# PocketQube.net
KiCad netlist of a schematic drawn in EAGLE
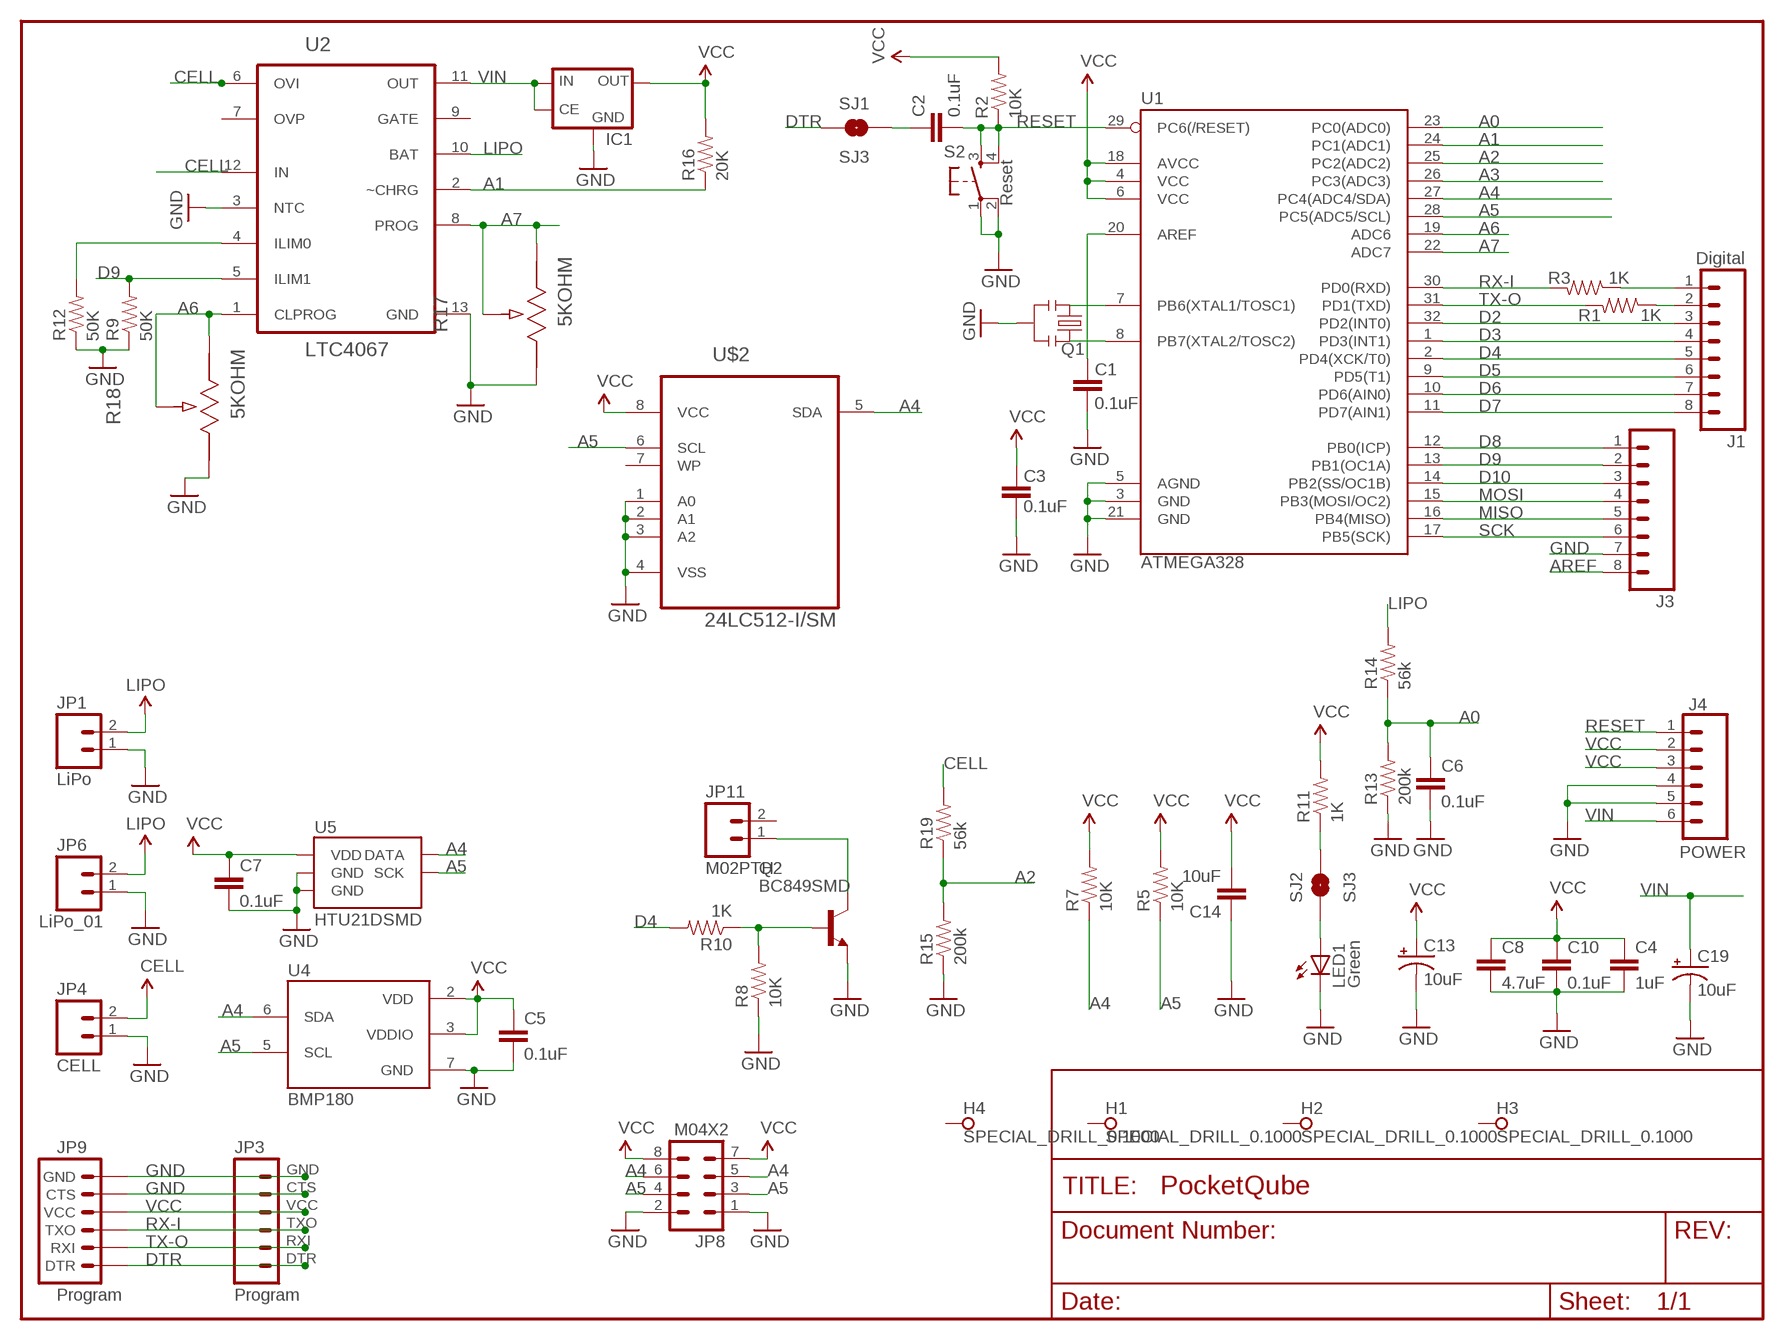
[diagram p0: schematic, sheet 1]

(export (version "E")
  (design (tool "Eeschema 10.0.6"))
  (components
    (comp (ref "C1")
      (value "0.1uF")
      (footprint "eagle-import:0805")
      (libsource (lib "eagle-import") (part "CAP0805"))
    )
    (comp (ref "C2")
      (value "0.1uF")
      (footprint "eagle-import:0805")
      (libsource (lib "eagle-import") (part "CAP0805"))
    )
    (comp (ref "C3")
      (value "0.1uF")
      (footprint "eagle-import:0805")
      (libsource (lib "eagle-import") (part "CAP0805"))
    )
    (comp (ref "C4")
      (value "1uF")
      (footprint "eagle-import:0805")
      (libsource (lib "eagle-import") (part "CAP0805"))
    )
    (comp (ref "C5")
      (value "0.1uF")
      (footprint "eagle-import:0805")
      (libsource (lib "eagle-import") (part "CAP0805"))
    )
    (comp (ref "C6")
      (value "0.1uF")
      (footprint "eagle-import:0805")
      (libsource (lib "eagle-import") (part "CAP0805"))
    )
    (comp (ref "C7")
      (value "0.1uF")
      (footprint "eagle-import:0805")
      (libsource (lib "eagle-import") (part "CAP0805"))
    )
    (comp (ref "C8")
      (value "4.7uF")
      (footprint "eagle-import:0805")
      (libsource (lib "eagle-import") (part "CAP0805"))
    )
    (comp (ref "C10")
      (value "0.1uF")
      (footprint "eagle-import:0805")
      (libsource (lib "eagle-import") (part "CAP0805"))
    )
    (comp (ref "C13")
      (value "10uF")
      (footprint "eagle-import:EIA3216")
      (libsource (lib "eagle-import") (part "CAP_POL1206"))
    )
    (comp (ref "C14")
      (value "10uF")
      (footprint "eagle-import:0805")
      (libsource (lib "eagle-import") (part "SparkFun-Passives_CAP0805"))
    )
    (comp (ref "C19")
      (value "10uF")
      (footprint "eagle-import:EIA3216")
      (libsource (lib "eagle-import") (part "CAP_POL1206"))
    )
    (comp (ref "H1")
      (value "SPECIAL_DRILL_0.1000")
      (footprint "eagle-import:PAD_0.1000")
      (libsource (lib "eagle-import") (part "SPECIAL_DRILL_0.1000"))
    )
    (comp (ref "H2")
      (value "SPECIAL_DRILL_0.1000")
      (footprint "eagle-import:PAD_0.1000")
      (libsource (lib "eagle-import") (part "SPECIAL_DRILL_0.1000"))
    )
    (comp (ref "H3")
      (value "SPECIAL_DRILL_0.1000")
      (footprint "eagle-import:PAD_0.1000")
      (libsource (lib "eagle-import") (part "SPECIAL_DRILL_0.1000"))
    )
    (comp (ref "H4")
      (value "SPECIAL_DRILL_0.1000")
      (footprint "eagle-import:PAD_0.1000")
      (libsource (lib "eagle-import") (part "SPECIAL_DRILL_0.1000"))
    )
    (comp (ref "IC1")
      (value "XC63FPP")
      (footprint "eagle-import:SOT89R")
      (libsource (lib "eagle-import") (part "XC63FPP"))
    )
    (comp (ref "J1")
      (value "Digital")
      (footprint "eagle-import:1X08")
      (libsource (lib "eagle-import") (part "M081X08"))
    )
    (comp (ref "J3")
      (value "M081X08")
      (footprint "eagle-import:1X08")
      (libsource (lib "eagle-import") (part "M081X08"))
    )
    (comp (ref "J4")
      (value "POWER")
      (footprint "eagle-import:1X06")
      (libsource (lib "eagle-import") (part "M06SIP"))
    )
    (comp (ref "JP1")
      (value "LiPo")
      (footprint "eagle-import:1X02")
      (libsource (lib "eagle-import") (part "SparkFun-Connectors_M02PTH"))
    )
    (comp (ref "JP3")
      (value "Program")
      (footprint "eagle-import:1X06")
      (libsource (lib "eagle-import") (part "SparkFun-Connectors_M06SIP"))
    )
    (comp (ref "JP4")
      (value "CELL")
      (footprint "eagle-import:1X02")
      (libsource (lib "eagle-import") (part "SparkFun-Connectors_M02PTH"))
    )
    (comp (ref "JP6")
      (value "LiPo_01")
      (footprint "eagle-import:1X02")
      (libsource (lib "eagle-import") (part "M02PTH"))
    )
    (comp (ref "JP8")
      (value "M04X2")
      (footprint "eagle-import:2X4")
      (libsource (lib "eagle-import") (part "M04X2"))
    )
    (comp (ref "JP9")
      (value "Program")
      (footprint "eagle-import:1X06-SMD")
      (libsource (lib "eagle-import") (part "ARDUINO_SERIAL_PROGRAMSMD"))
    )
    (comp (ref "JP11")
      (value "M02PTH")
      (footprint "eagle-import:1X02")
      (libsource (lib "eagle-import") (part "SparkFun-Connectors_M02PTH"))
    )
    (comp (ref "LED1")
      (value "Green")
      (footprint "eagle-import:PLCC2")
      (libsource (lib "eagle-import") (part "_T679-?-1E1F1LG"))
    )
    (comp (ref "Q1")
      (value "8MHZ")
      (footprint "eagle-import:RESONATOR-SMD")
      (libsource (lib "eagle-import") (part "RESONATOR8MHZ"))
    )
    (comp (ref "Q2")
      (value "BC849SMD")
      (footprint "eagle-import:SOT23-BEC")
      (libsource (lib "eagle-import") (part "BC849SMD"))
    )
    (comp (ref "R1")
      (value "1K")
      (footprint "eagle-import:0805")
      (libsource (lib "eagle-import") (part "RESISTOR0805-RES"))
    )
    (comp (ref "R2")
      (value "10K")
      (footprint "eagle-import:0805")
      (libsource (lib "eagle-import") (part "RESISTOR0805-RES"))
    )
    (comp (ref "R3")
      (value "1K")
      (footprint "eagle-import:0805")
      (libsource (lib "eagle-import") (part "RESISTOR0805-RES"))
    )
    (comp (ref "R5")
      (value "10K")
      (footprint "eagle-import:0805")
      (libsource (lib "eagle-import") (part "RESISTOR0805-RES"))
    )
    (comp (ref "R7")
      (value "10K")
      (footprint "eagle-import:0805")
      (libsource (lib "eagle-import") (part "RESISTOR0805-RES"))
    )
    (comp (ref "R8")
      (value "10K")
      (footprint "eagle-import:0805")
      (libsource (lib "eagle-import") (part "RESISTOR0805-RES"))
    )
    (comp (ref "R9")
      (value "50K")
      (footprint "eagle-import:0805")
      (libsource (lib "eagle-import") (part "RESISTOR0805-RES"))
    )
    (comp (ref "R10")
      (value "1K")
      (footprint "eagle-import:0805")
      (libsource (lib "eagle-import") (part "RESISTOR0805-RES"))
    )
    (comp (ref "R11")
      (value "1K")
      (footprint "eagle-import:0805")
      (libsource (lib "eagle-import") (part "RESISTOR0805-RES"))
    )
    (comp (ref "R12")
      (value "50K")
      (footprint "eagle-import:0805")
      (libsource (lib "eagle-import") (part "RESISTOR0805-RES"))
    )
    (comp (ref "R13")
      (value "200k")
      (footprint "eagle-import:0805")
      (libsource (lib "eagle-import") (part "RESISTOR0805-RES"))
    )
    (comp (ref "R14")
      (value "56k")
      (footprint "eagle-import:0805")
      (libsource (lib "eagle-import") (part "RESISTOR0805-RES"))
    )
    (comp (ref "R15")
      (value "200k")
      (footprint "eagle-import:0805")
      (libsource (lib "eagle-import") (part "RESISTOR0805-RES"))
    )
    (comp (ref "R16")
      (value "20K")
      (footprint "eagle-import:0805")
      (libsource (lib "eagle-import") (part "RESISTOR0805-RES"))
    )
    (comp (ref "R17")
      (value "5KOHM")
      (footprint "eagle-import:POT_EVM2N")
      (fields (field (name "MPN") "EVM2NSX80B53") (field (name "TOLERANCE") "±25 %"))
      (libsource (lib "eagle-import") (part "EVM-2N2NSX80B53"))
    )
    (comp (ref "R18")
      (value "5KOHM")
      (footprint "eagle-import:POT_EVM2N")
      (fields (field (name "MPN") "EVM2NSX80B53") (field (name "TOLERANCE") "±25 %"))
      (libsource (lib "eagle-import") (part "EVM-2N2NSX80B53"))
    )
    (comp (ref "R19")
      (value "56k")
      (footprint "eagle-import:0805")
      (libsource (lib "eagle-import") (part "RESISTOR0805-RES"))
    )
    (comp (ref "S2")
      (value "Reset")
      (footprint "eagle-import:TACTILE_SWITCH_SMD")
      (libsource (lib "eagle-import") (part "TAC_SWITCHSMD"))
    )
    (comp (ref "SJ1")
      (value "SJ3")
      (footprint "eagle-import:SJ_2S-NOTRACE")
      (libsource (lib "eagle-import") (part "SOLDERJUMPERNC2"))
    )
    (comp (ref "SJ2")
      (value "SJ3")
      (footprint "eagle-import:SJ_2S-NOTRACE")
      (libsource (lib "eagle-import") (part "SOLDERJUMPERNC2"))
    )
    (comp (ref "U$2")
      (value "24LC512-I/SM")
      (footprint "eagle-import:SOIC127P794X203-8N")
      (libsource (lib "eagle-import") (part "24LC512-I/SM"))
    )
    (comp (ref "U1")
      (value "ATMEGA328")
      (footprint "eagle-import:TQFP32-08")
      (libsource (lib "eagle-import") (part "ATMEGA168"))
    )
    (comp (ref "U2")
      (value "LTC4067")
      (footprint "eagle-import:DFN300X300X80-13N")
      (fields (field (name "MPN") "LT3652EDD#PBF"))
      (libsource (lib "eagle-import") (part "LT3652EDDPBF"))
    )
    (comp (ref "U4")
      (value "BMP180")
      (footprint "eagle-import:BMP180")
      (libsource (lib "eagle-import") (part "BMP180"))
    )
    (comp (ref "U5")
      (value "HTU21DSMD")
      (footprint "eagle-import:HTU21D")
      (libsource (lib "eagle-import") (part "HTU21DSMD"))
    )
  )
  (nets
    (net (code "1") (name "/A0") (class "Default")
      (node (ref "C6") (pin "1") (pinfunction "1_1") (pintype "passive"))
      (node (ref "R13") (pin "2") (pinfunction "2_2") (pintype "passive"))
      (node (ref "R14") (pin "1") (pinfunction "1_1") (pintype "passive"))
      (node (ref "U1") (pin "23") (pinfunction "PC0(ADC0)_23") (pintype "bidirectional"))
    )
    (net (code "2") (name "/A1") (class "Default")
      (node (ref "R16") (pin "1") (pinfunction "1_1") (pintype "passive"))
      (node (ref "U1") (pin "24") (pinfunction "PC1(ADC1)_24") (pintype "bidirectional"))
      (node (ref "U2") (pin "2") (pinfunction "~{CHRG}_2") (pintype "output"))
    )
    (net (code "3") (name "/A2") (class "Default")
      (node (ref "R15") (pin "2") (pinfunction "2_2") (pintype "passive"))
      (node (ref "R19") (pin "1") (pinfunction "1_1") (pintype "passive"))
      (node (ref "U1") (pin "25") (pinfunction "PC2(ADC2)_25") (pintype "bidirectional"))
    )
    (net (code "4") (name "/A3") (class "Default")
      (node (ref "U1") (pin "26") (pinfunction "PC3(ADC3)_26") (pintype "bidirectional"))
    )
    (net (code "5") (name "/A4") (class "Default")
      (node (ref "JP8") (pin "5") (pinfunction "5_5") (pintype "passive"))
      (node (ref "JP8") (pin "6") (pinfunction "6_6") (pintype "passive"))
      (node (ref "R7") (pin "1") (pinfunction "1_1") (pintype "passive"))
      (node (ref "U$2") (pin "5") (pinfunction "SDA_5") (pintype "bidirectional"))
      (node (ref "U1") (pin "27") (pinfunction "PC4(ADC4/SDA)_27") (pintype "bidirectional"))
      (node (ref "U4") (pin "6") (pinfunction "SDA_6") (pintype "bidirectional"))
      (node (ref "U5") (pin "DATA") (pinfunction "DATA_DATA") (pintype "bidirectional"))
    )
    (net (code "6") (name "/A5") (class "Default")
      (node (ref "JP8") (pin "3") (pinfunction "3_3") (pintype "passive"))
      (node (ref "JP8") (pin "4") (pinfunction "4_4") (pintype "passive"))
      (node (ref "R5") (pin "1") (pinfunction "1_1") (pintype "passive"))
      (node (ref "U$2") (pin "6") (pinfunction "SCL_6") (pintype "input"))
      (node (ref "U1") (pin "28") (pinfunction "PC5(ADC5/SCL)_28") (pintype "bidirectional"))
      (node (ref "U4") (pin "5") (pinfunction "SCL_5") (pintype "input"))
      (node (ref "U5") (pin "SCK") (pinfunction "SCK_SCK") (pintype "input"))
    )
    (net (code "7") (name "/A6") (class "Default")
      (node (ref "R18") (pin "2") (pinfunction "2_2") (pintype "passive"))
      (node (ref "R18") (pin "3") (pinfunction "3_3") (pintype "passive"))
      (node (ref "U1") (pin "19") (pinfunction "ADC6_19") (pintype "bidirectional"))
      (node (ref "U2") (pin "1") (pinfunction "CLPROG_1") (pintype "input"))
    )
    (net (code "8") (name "/A7") (class "Default")
      (node (ref "R17") (pin "2") (pinfunction "2_2") (pintype "passive"))
      (node (ref "R17") (pin "3") (pinfunction "3_3") (pintype "passive"))
      (node (ref "U1") (pin "22") (pinfunction "ADC7_22") (pintype "bidirectional"))
      (node (ref "U2") (pin "8") (pinfunction "PROG_8") (pintype "input"))
    )
    (net (code "9") (name "/AREF") (class "Default")
      (node (ref "C1") (pin "2") (pinfunction "2_2") (pintype "passive"))
      (node (ref "J3") (pin "8") (pinfunction "8_8") (pintype "passive"))
      (node (ref "U1") (pin "20") (pinfunction "AREF_20") (pintype "bidirectional"))
    )
    (net (code "10") (name "/D2") (class "Default")
      (node (ref "J1") (pin "3") (pinfunction "3_3") (pintype "passive"))
      (node (ref "U1") (pin "32") (pinfunction "PD2(INT0)_32") (pintype "bidirectional"))
    )
    (net (code "11") (name "/D3") (class "Default")
      (node (ref "J1") (pin "4") (pinfunction "4_4") (pintype "passive"))
      (node (ref "U1") (pin "1") (pinfunction "PD3(INT1)_1") (pintype "bidirectional"))
    )
    (net (code "12") (name "/D4") (class "Default")
      (node (ref "J1") (pin "5") (pinfunction "5_5") (pintype "passive"))
      (node (ref "R10") (pin "2") (pinfunction "2_2") (pintype "passive"))
      (node (ref "U1") (pin "2") (pinfunction "PD4(XCK/T0)_2") (pintype "bidirectional"))
    )
    (net (code "13") (name "/D5") (class "Default")
      (node (ref "J1") (pin "6") (pinfunction "6_6") (pintype "passive"))
      (node (ref "U1") (pin "9") (pinfunction "PD5(T1)_9") (pintype "bidirectional"))
    )
    (net (code "14") (name "/D6") (class "Default")
      (node (ref "J1") (pin "7") (pinfunction "7_7") (pintype "passive"))
      (node (ref "U1") (pin "10") (pinfunction "PD6(AIN0)_10") (pintype "bidirectional"))
    )
    (net (code "15") (name "/D7") (class "Default")
      (node (ref "J1") (pin "8") (pinfunction "8_8") (pintype "passive"))
      (node (ref "U1") (pin "11") (pinfunction "PD7(AIN1)_11") (pintype "bidirectional"))
    )
    (net (code "16") (name "/D8") (class "Default")
      (node (ref "J3") (pin "1") (pinfunction "1_1") (pintype "passive"))
      (node (ref "U1") (pin "12") (pinfunction "PB0(ICP)_12") (pintype "bidirectional"))
    )
    (net (code "17") (name "/D9") (class "Default")
      (node (ref "J3") (pin "2") (pinfunction "2_2") (pintype "passive"))
      (node (ref "R9") (pin "2") (pinfunction "2_2") (pintype "passive"))
      (node (ref "U1") (pin "13") (pinfunction "PB1(OC1A)_13") (pintype "bidirectional"))
      (node (ref "U2") (pin "5") (pinfunction "ILIM1_5") (pintype "input"))
    )
    (net (code "18") (name "/D10") (class "Default")
      (node (ref "J3") (pin "3") (pinfunction "3_3") (pintype "passive"))
      (node (ref "U1") (pin "14") (pinfunction "PB2(SS/OC1B)_14") (pintype "bidirectional"))
    )
    (net (code "19") (name "/DTR") (class "Default")
      (node (ref "JP3") (pin "DTR") (pinfunction "1_DTR") (pintype "passive"))
      (node (ref "JP9") (pin "1") (pinfunction "DTR_1") (pintype "passive"))
      (node (ref "SJ1") (pin "1") (pinfunction "1_1") (pintype "passive"))
    )
    (net (code "20") (name "/MISO") (class "Default")
      (node (ref "J3") (pin "5") (pinfunction "5_5") (pintype "passive"))
      (node (ref "U1") (pin "16") (pinfunction "PB4(MISO)_16") (pintype "bidirectional"))
    )
    (net (code "21") (name "/MOSI") (class "Default")
      (node (ref "J3") (pin "4") (pinfunction "4_4") (pintype "passive"))
      (node (ref "U1") (pin "15") (pinfunction "PB3(MOSI/OC2)_15") (pintype "bidirectional"))
    )
    (net (code "22") (name "/RESET") (class "Default")
      (node (ref "C2") (pin "2") (pinfunction "2_2") (pintype "passive"))
      (node (ref "J4") (pin "1") (pinfunction "1_1") (pintype "passive"))
      (node (ref "R2") (pin "1") (pinfunction "1_1") (pintype "passive"))
      (node (ref "S2") (pin "3") (pinfunction "3_3") (pintype "passive"))
      (node (ref "S2") (pin "4") (pinfunction "4_4") (pintype "passive"))
      (node (ref "U1") (pin "29") (pinfunction "PC6(/RESET)_29") (pintype "bidirectional"))
    )
    (net (code "23") (name "/RX-I") (class "Default")
      (node (ref "JP3") (pin "TXO") (pinfunction "3_TXO") (pintype "passive"))
      (node (ref "JP9") (pin "3") (pinfunction "TXO_3") (pintype "passive"))
      (node (ref "R3") (pin "2") (pinfunction "2_2") (pintype "passive"))
      (node (ref "U1") (pin "30") (pinfunction "PD0(RXD)_30") (pintype "bidirectional"))
    )
    (net (code "24") (name "/SCK") (class "Default")
      (node (ref "J3") (pin "6") (pinfunction "6_6") (pintype "passive"))
      (node (ref "U1") (pin "17") (pinfunction "PB5(SCK)_17") (pintype "bidirectional"))
    )
    (net (code "25") (name "/TX-O") (class "Default")
      (node (ref "JP3") (pin "RXI") (pinfunction "2_RXI") (pintype "passive"))
      (node (ref "JP9") (pin "2") (pinfunction "RXI_2") (pintype "passive"))
      (node (ref "R1") (pin "2") (pinfunction "2_2") (pintype "passive"))
      (node (ref "U1") (pin "31") (pinfunction "PD1(TXD)_31") (pintype "bidirectional"))
    )
    (net (code "26") (name "/VIN") (class "Default")
      (node (ref "C19") (pin "A") (pinfunction "+_A") (pintype "passive"))
      (node (ref "IC1") (pin "1") (pinfunction "CE_1") (pintype "input"))
      (node (ref "IC1") (pin "4") (pinfunction "IN_4") (pintype "input"))
      (node (ref "J4") (pin "6") (pinfunction "6_6") (pintype "passive"))
      (node (ref "U2") (pin "11") (pinfunction "OUT_11") (pintype "output"))
    )
    (net (code "27") (name "CELL") (class "Default")
      (node (ref "JP4") (pin "2") (pinfunction "2_2") (pintype "passive"))
      (node (ref "R19") (pin "2") (pinfunction "2_2") (pintype "passive"))
      (node (ref "U2") (pin "12") (pinfunction "IN_12") (pintype "power_in"))
      (node (ref "U2") (pin "6") (pinfunction "OVI_6") (pintype "input"))
    )
    (net (code "28") (name "GND") (class "Default")
      (node (ref "C1") (pin "1") (pinfunction "1_1") (pintype "passive"))
      (node (ref "C10") (pin "2") (pinfunction "2_2") (pintype "passive"))
      (node (ref "C13") (pin "C") (pinfunction "-_C") (pintype "passive"))
      (node (ref "C14") (pin "1") (pinfunction "1_1") (pintype "passive"))
      (node (ref "C19") (pin "C") (pinfunction "-_C") (pintype "passive"))
      (node (ref "C3") (pin "1") (pinfunction "1_1") (pintype "passive"))
      (node (ref "C4") (pin "2") (pinfunction "2_2") (pintype "passive"))
      (node (ref "C5") (pin "2") (pinfunction "2_2") (pintype "passive"))
      (node (ref "C6") (pin "2") (pinfunction "2_2") (pintype "passive"))
      (node (ref "C7") (pin "2") (pinfunction "2_2") (pintype "passive"))
      (node (ref "C8") (pin "2") (pinfunction "2_2") (pintype "passive"))
      (node (ref "IC1") (pin "2") (pinfunction "GND_2") (pintype "power_in"))
      (node (ref "J3") (pin "7") (pinfunction "7_7") (pintype "passive"))
      (node (ref "J4") (pin "4") (pinfunction "4_4") (pintype "passive"))
      (node (ref "J4") (pin "5") (pinfunction "5_5") (pintype "passive"))
      (node (ref "JP1") (pin "1") (pinfunction "1_1") (pintype "passive"))
      (node (ref "JP3") (pin "CTS") (pinfunction "5_CTS") (pintype "passive"))
      (node (ref "JP3") (pin "GND") (pinfunction "6_GND") (pintype "passive"))
      (node (ref "JP4") (pin "1") (pinfunction "1_1") (pintype "passive"))
      (node (ref "JP6") (pin "1") (pinfunction "1_1") (pintype "passive"))
      (node (ref "JP8") (pin "1") (pinfunction "1_1") (pintype "passive"))
      (node (ref "JP8") (pin "2") (pinfunction "2_2") (pintype "passive"))
      (node (ref "JP9") (pin "5") (pinfunction "CTS_5") (pintype "passive"))
      (node (ref "JP9") (pin "6") (pinfunction "GND_6") (pintype "passive"))
      (node (ref "LED1") (pin "C") (pinfunction "C_C") (pintype "passive"))
      (node (ref "Q1") (pin "2") (pinfunction "2_2") (pintype "passive"))
      (node (ref "Q2") (pin "E") (pinfunction "E_E") (pintype "passive"))
      (node (ref "R12") (pin "1") (pinfunction "1_1") (pintype "passive"))
      (node (ref "R13") (pin "1") (pinfunction "1_1") (pintype "passive"))
      (node (ref "R15") (pin "1") (pinfunction "1_1") (pintype "passive"))
      (node (ref "R17") (pin "1") (pinfunction "1_1") (pintype "passive"))
      (node (ref "R18") (pin "1") (pinfunction "1_1") (pintype "passive"))
      (node (ref "R8") (pin "1") (pinfunction "1_1") (pintype "passive"))
      (node (ref "R9") (pin "1") (pinfunction "1_1") (pintype "passive"))
      (node (ref "S2") (pin "1") (pinfunction "1_1") (pintype "passive"))
      (node (ref "S2") (pin "2") (pinfunction "2_2") (pintype "passive"))
      (node (ref "U$2") (pin "1") (pinfunction "A0_1") (pintype "input"))
      (node (ref "U$2") (pin "2") (pinfunction "A1_2") (pintype "input"))
      (node (ref "U$2") (pin "3") (pinfunction "A2_3") (pintype "input"))
      (node (ref "U$2") (pin "4") (pinfunction "VSS_4") (pintype "passive"))
      (node (ref "U1") (pin "21") (pinfunction "GND_21") (pintype "bidirectional"))
      (node (ref "U1") (pin "3") (pinfunction "GND_3") (pintype "bidirectional"))
      (node (ref "U1") (pin "5") (pinfunction "AGND_5") (pintype "bidirectional"))
      (node (ref "U2") (pin "13") (pinfunction "GND_13") (pintype "passive"))
      (node (ref "U2") (pin "3") (pinfunction "NTC_3") (pintype "input"))
      (node (ref "U4") (pin "7") (pinfunction "GND_7") (pintype "power_in"))
      (node (ref "U5") (pin "7") (pinfunction "GND_7") (pintype "power_in"))
      (node (ref "U5") (pin "GND") (pinfunction "GND_GND") (pintype "power_in"))
    )
    (net (code "29") (name "LIPO") (class "Default")
      (node (ref "JP1") (pin "2") (pinfunction "2_2") (pintype "passive"))
      (node (ref "JP6") (pin "2") (pinfunction "2_2") (pintype "passive"))
      (node (ref "R14") (pin "2") (pinfunction "2_2") (pintype "passive"))
      (node (ref "U2") (pin "10") (pinfunction "BAT_10") (pintype "output"))
    )
    (net (code "30") (name "Net-(C2-Pad1)") (class "Default")
      (node (ref "C2") (pin "1") (pinfunction "1_1") (pintype "passive"))
      (node (ref "SJ1") (pin "2") (pinfunction "2_2") (pintype "passive"))
    )
    (net (code "31") (name "Net-(J1-Pad1)") (class "Default")
      (node (ref "J1") (pin "1") (pinfunction "1_1") (pintype "passive"))
      (node (ref "R3") (pin "1") (pinfunction "1_1") (pintype "passive"))
    )
    (net (code "32") (name "Net-(J1-Pad2)") (class "Default")
      (node (ref "J1") (pin "2") (pinfunction "2_2") (pintype "passive"))
      (node (ref "R1") (pin "1") (pinfunction "1_1") (pintype "passive"))
    )
    (net (code "33") (name "Net-(JP11-Pad1)") (class "Default")
      (node (ref "JP11") (pin "1") (pinfunction "1_1") (pintype "passive"))
      (node (ref "Q2") (pin "C") (pinfunction "C_C") (pintype "passive"))
    )
    (net (code "34") (name "Net-(LED1-PadA)") (class "Default")
      (node (ref "LED1") (pin "A") (pinfunction "A_A") (pintype "passive"))
      (node (ref "SJ2") (pin "1") (pinfunction "1_1") (pintype "passive"))
    )
    (net (code "35") (name "Net-(Q2-PadB)") (class "Default")
      (node (ref "Q2") (pin "B") (pinfunction "B_B") (pintype "passive"))
      (node (ref "R10") (pin "1") (pinfunction "1_1") (pintype "passive"))
      (node (ref "R8") (pin "2") (pinfunction "2_2") (pintype "passive"))
    )
    (net (code "36") (name "Net-(R11-Pad1)") (class "Default")
      (node (ref "R11") (pin "1") (pinfunction "1_1") (pintype "passive"))
      (node (ref "SJ2") (pin "2") (pinfunction "2_2") (pintype "passive"))
    )
    (net (code "37") (name "Net-(U1-PB6(XTAL1{slash}TOSC1))") (class "Default")
      (node (ref "Q1") (pin "3") (pinfunction "3_3") (pintype "passive"))
      (node (ref "U1") (pin "7") (pinfunction "PB6(XTAL1/TOSC1)_7") (pintype "bidirectional"))
    )
    (net (code "38") (name "Net-(U1-PB7(XTAL2{slash}TOSC2))") (class "Default")
      (node (ref "Q1") (pin "1") (pinfunction "1_1") (pintype "passive"))
      (node (ref "U1") (pin "8") (pinfunction "PB7(XTAL2/TOSC2)_8") (pintype "bidirectional"))
    )
    (net (code "39") (name "Net-(U2-ILIM0)") (class "Default")
      (node (ref "R12") (pin "2") (pinfunction "2_2") (pintype "passive"))
      (node (ref "U2") (pin "4") (pinfunction "ILIM0_4") (pintype "input"))
    )
    (net (code "40") (name "VCC") (class "Default")
      (node (ref "C10") (pin "1") (pinfunction "1_1") (pintype "passive"))
      (node (ref "C13") (pin "A") (pinfunction "+_A") (pintype "passive"))
      (node (ref "C14") (pin "2") (pinfunction "2_2") (pintype "passive"))
      (node (ref "C3") (pin "2") (pinfunction "2_2") (pintype "passive"))
      (node (ref "C4") (pin "1") (pinfunction "1_1") (pintype "passive"))
      (node (ref "C5") (pin "1") (pinfunction "1_1") (pintype "passive"))
      (node (ref "C7") (pin "1") (pinfunction "1_1") (pintype "passive"))
      (node (ref "C8") (pin "1") (pinfunction "1_1") (pintype "passive"))
      (node (ref "IC1") (pin "5") (pinfunction "OUT_5") (pintype "output"))
      (node (ref "J4") (pin "2") (pinfunction "2_2") (pintype "passive"))
      (node (ref "J4") (pin "3") (pinfunction "3_3") (pintype "passive"))
      (node (ref "JP3") (pin "VCC") (pinfunction "4_VCC") (pintype "passive"))
      (node (ref "JP8") (pin "7") (pinfunction "7_7") (pintype "passive"))
      (node (ref "JP8") (pin "8") (pinfunction "8_8") (pintype "passive"))
      (node (ref "JP9") (pin "4") (pinfunction "VCC_4") (pintype "passive"))
      (node (ref "R11") (pin "2") (pinfunction "2_2") (pintype "passive"))
      (node (ref "R16") (pin "2") (pinfunction "2_2") (pintype "passive"))
      (node (ref "R2") (pin "2") (pinfunction "2_2") (pintype "passive"))
      (node (ref "R5") (pin "2") (pinfunction "2_2") (pintype "passive"))
      (node (ref "R7") (pin "2") (pinfunction "2_2") (pintype "passive"))
      (node (ref "U$2") (pin "8") (pinfunction "VCC_8") (pintype "power_in"))
      (node (ref "U1") (pin "18") (pinfunction "AVCC_18") (pintype "bidirectional"))
      (node (ref "U1") (pin "4") (pinfunction "VCC_4") (pintype "bidirectional"))
      (node (ref "U1") (pin "6") (pinfunction "VCC_6") (pintype "bidirectional"))
      (node (ref "U4") (pin "2") (pinfunction "VDD_2") (pintype "power_in"))
      (node (ref "U4") (pin "3") (pinfunction "VDDIO_3") (pintype "power_in"))
      (node (ref "U5") (pin "VDD") (pinfunction "VDD_VDD") (pintype "power_in"))
    )
    (net (code "41") (name "unconnected-(H1-Pad1)") (class "Default")
      (node (ref "H1") (pin "1") (pinfunction "1_1") (pintype "passive"))
    )
    (net (code "42") (name "unconnected-(H2-Pad1)") (class "Default")
      (node (ref "H2") (pin "1") (pinfunction "1_1") (pintype "passive"))
    )
    (net (code "43") (name "unconnected-(H3-Pad1)") (class "Default")
      (node (ref "H3") (pin "1") (pinfunction "1_1") (pintype "passive"))
    )
    (net (code "44") (name "unconnected-(H4-Pad1)") (class "Default")
      (node (ref "H4") (pin "1") (pinfunction "1_1") (pintype "passive"))
    )
    (net (code "45") (name "unconnected-(JP11-Pad2)") (class "Default")
      (node (ref "JP11") (pin "2") (pinfunction "2_2") (pintype "passive"))
    )
    (net (code "46") (name "unconnected-(U$2-WP-Pad7)") (class "Default")
      (node (ref "U$2") (pin "7") (pinfunction "WP_7") (pintype "input"))
    )
    (net (code "47") (name "unconnected-(U2-GATE-Pad9)") (class "Default")
      (node (ref "U2") (pin "9") (pinfunction "GATE_9") (pintype "output"))
    )
    (net (code "48") (name "unconnected-(U2-OVP-Pad7)") (class "Default")
      (node (ref "U2") (pin "7") (pinfunction "OVP_7") (pintype "input"))
    )
  )
)
